# esp32_feather.net
KiCad netlist of a schematic drawn in EAGLE
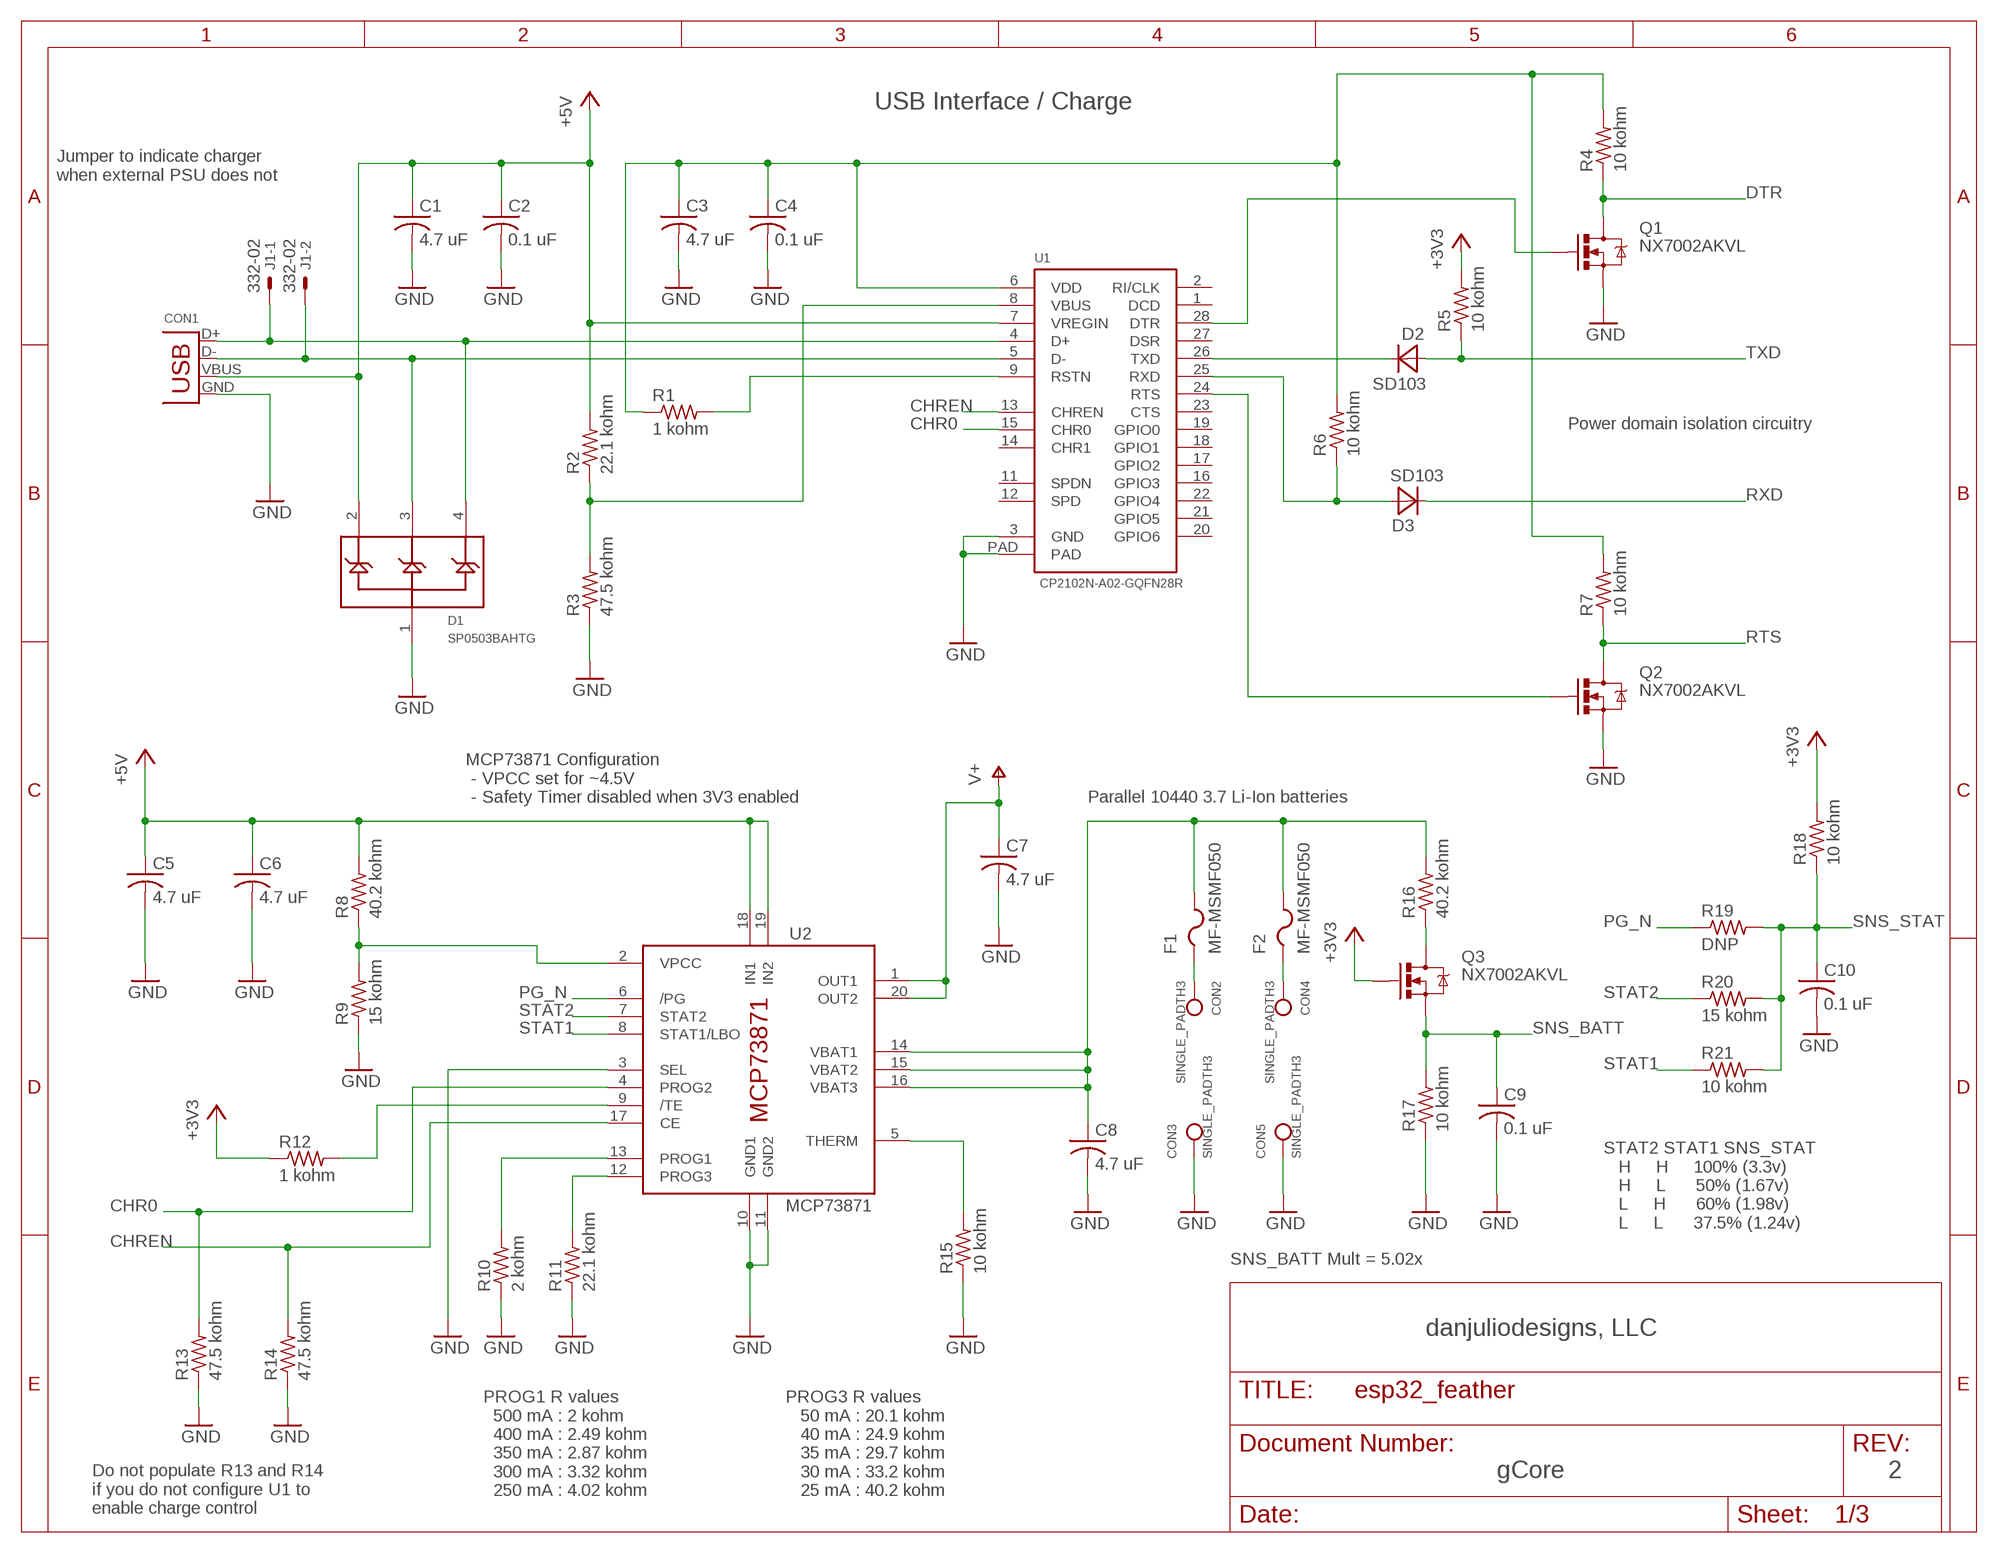
[diagram p0: schematic, sheet 1]
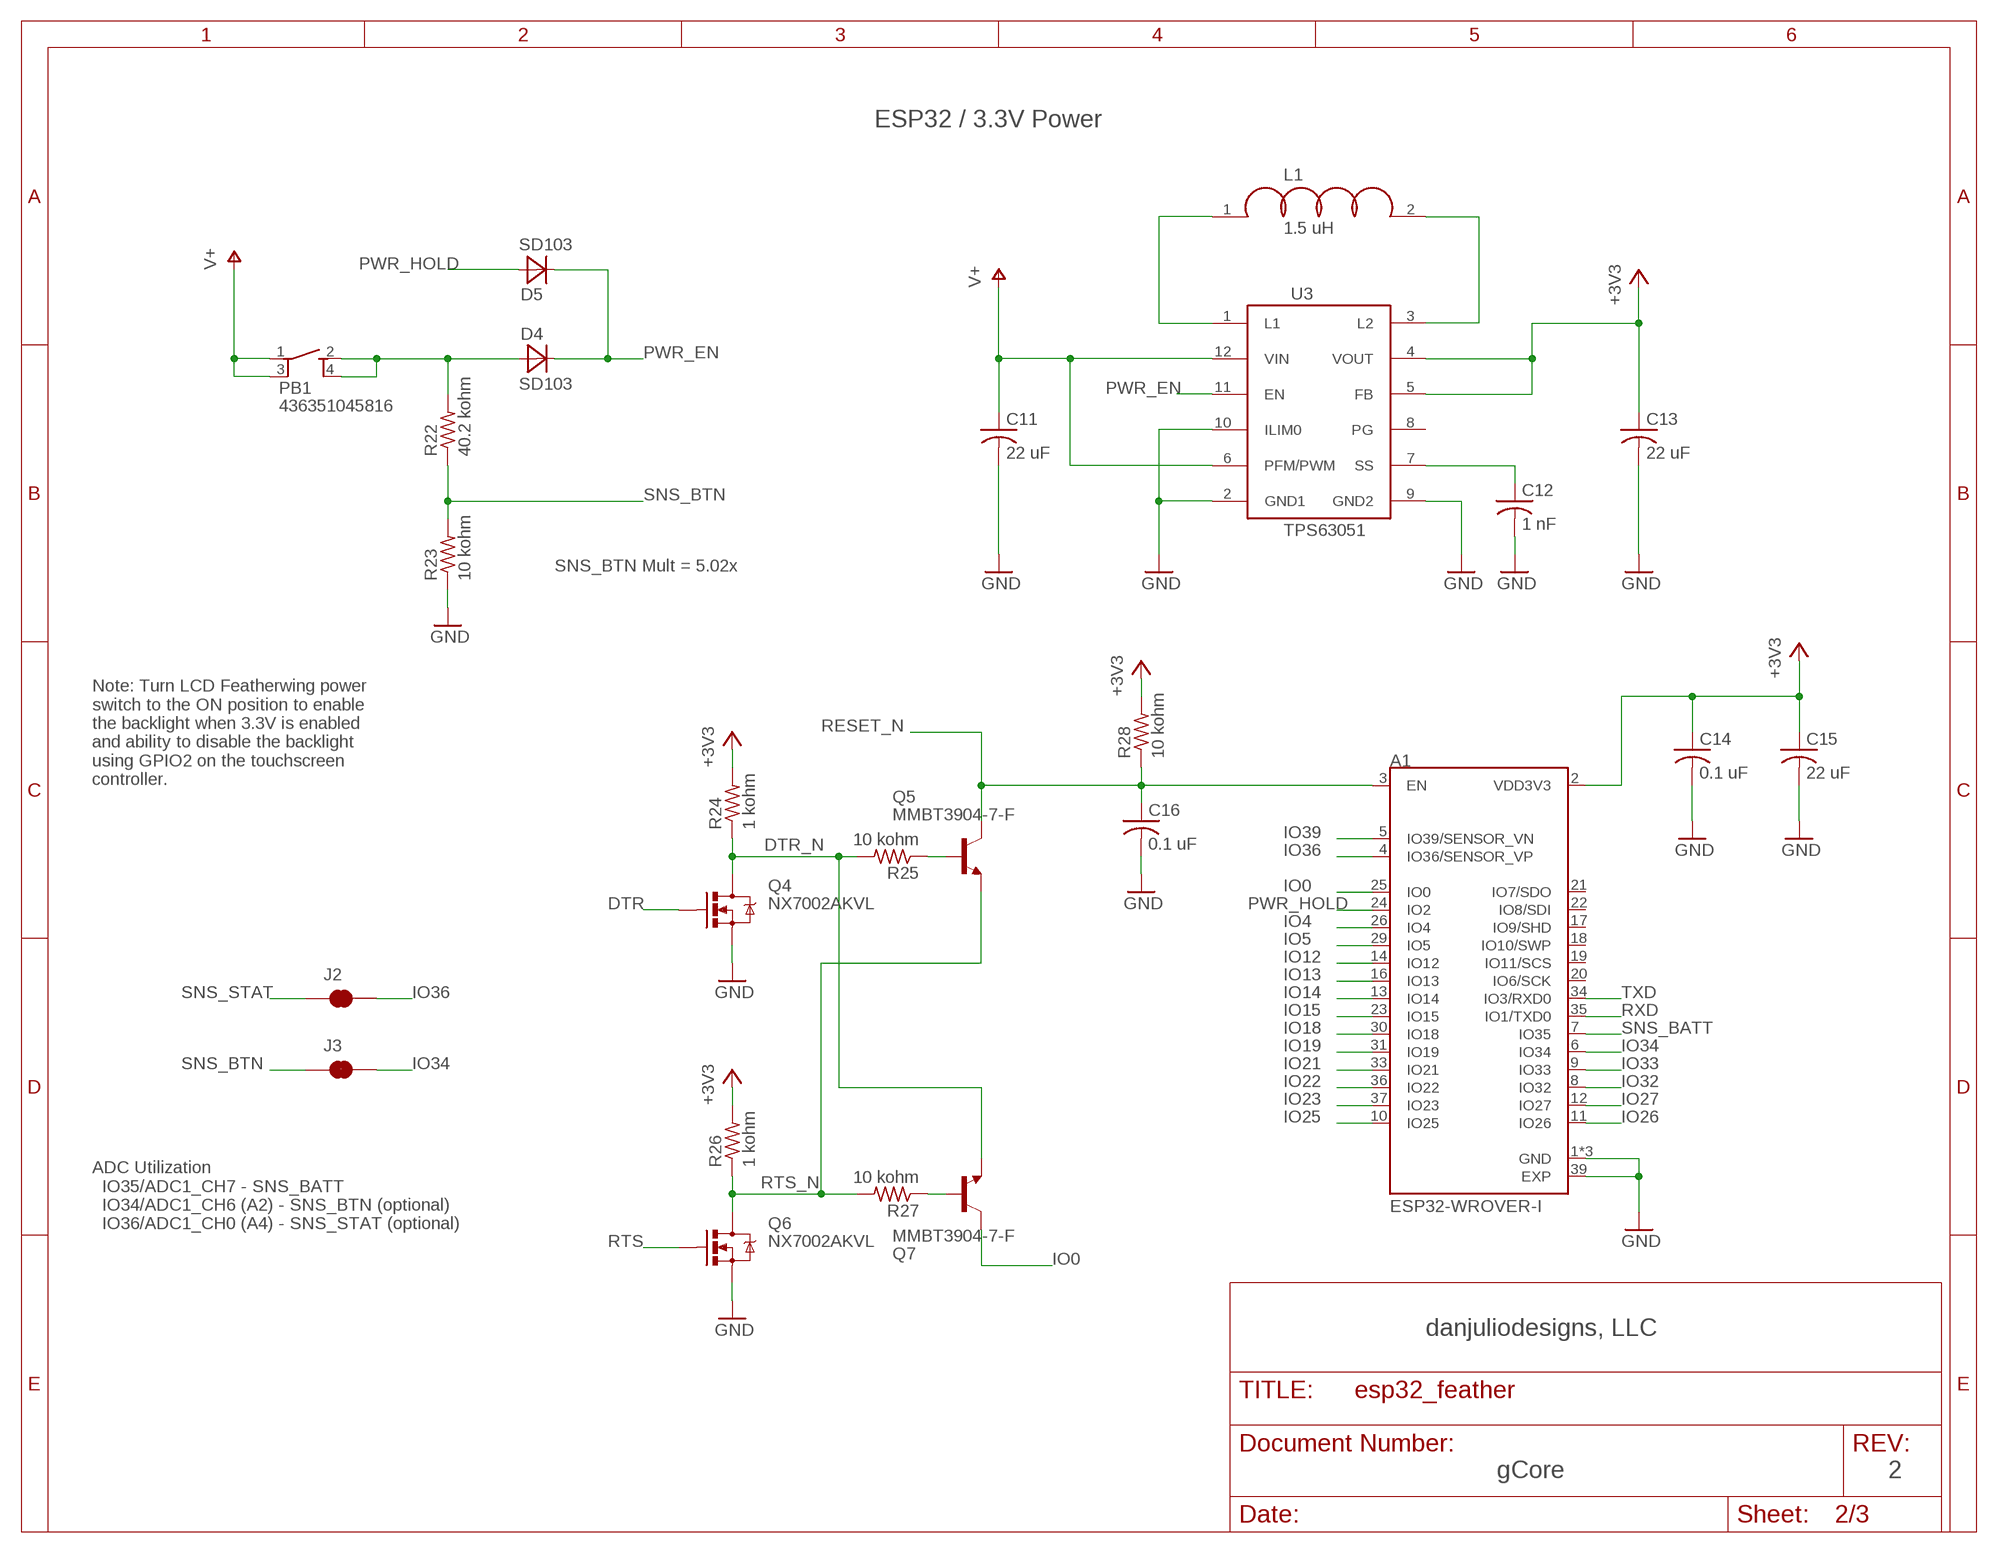
[diagram p1: schematic, sheet 2]
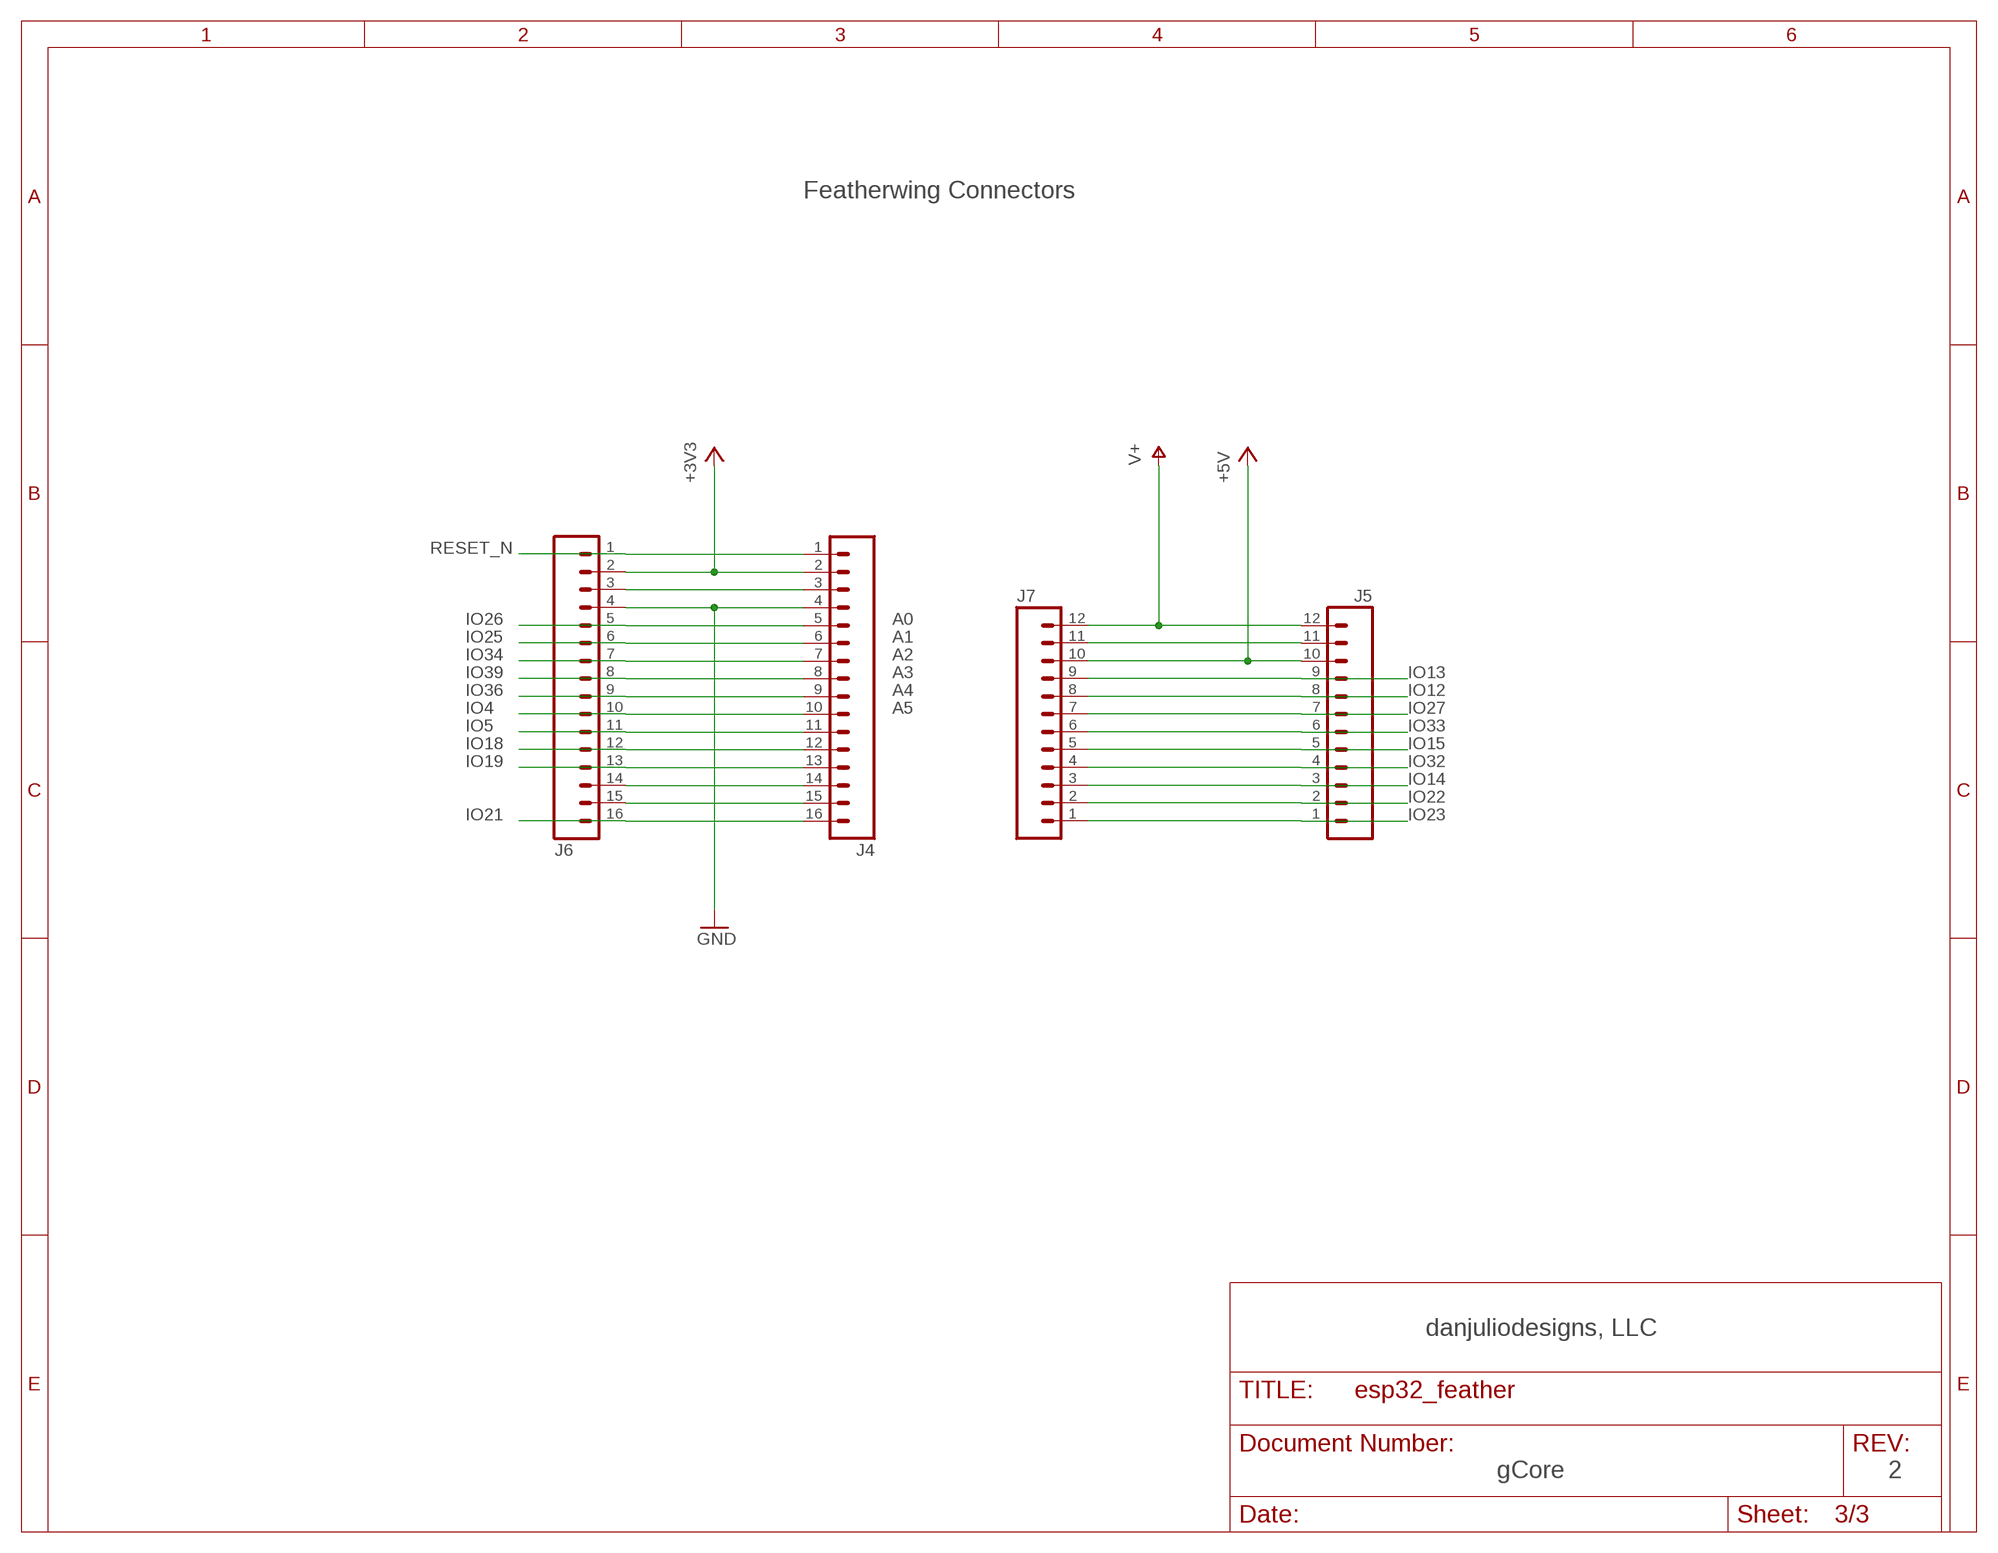
[diagram p2: schematic, sheet 3]

(export (version "E")
  (design (tool "Eeschema 10.0.6"))
  (components
    (comp (ref "C1")
      (value "4.7 uF")
      (footprint "eagle-import:C0603")
      (libsource (lib "eagle-import") (part "C-USSMT0603"))
    )
    (comp (ref "C2")
      (value "0.1 uF")
      (footprint "eagle-import:C0603")
      (libsource (lib "eagle-import") (part "C-USSMT0603"))
    )
    (comp (ref "C3")
      (value "4.7 uF")
      (footprint "eagle-import:C0603")
      (libsource (lib "eagle-import") (part "C-USSMT0603"))
    )
    (comp (ref "C4")
      (value "0.1 uF")
      (footprint "eagle-import:C0603")
      (libsource (lib "eagle-import") (part "C-USSMT0603"))
    )
    (comp (ref "C5")
      (value "4.7 uF")
      (footprint "eagle-import:C0603")
      (libsource (lib "eagle-import") (part "C-USSMT0603"))
    )
    (comp (ref "C6")
      (value "4.7 uF")
      (footprint "eagle-import:C0603")
      (libsource (lib "eagle-import") (part "C-USSMT0603"))
    )
    (comp (ref "C7")
      (value "4.7 uF")
      (footprint "eagle-import:C0603")
      (libsource (lib "eagle-import") (part "C-USSMT0603"))
    )
    (comp (ref "C8")
      (value "4.7 uF")
      (footprint "eagle-import:C0603")
      (libsource (lib "eagle-import") (part "C-USSMT0603"))
    )
    (comp (ref "C9")
      (value "0.1 uF")
      (footprint "eagle-import:C0603")
      (libsource (lib "eagle-import") (part "C-USSMT0603"))
    )
    (comp (ref "C10")
      (value "0.1 uF")
      (footprint "eagle-import:C0603")
      (libsource (lib "eagle-import") (part "C-USSMT0603"))
    )
    (comp (ref "CON1")
      (value "USBMICROB")
      (footprint "eagle-import:USB_MICROB_SMT")
      (libsource (lib "eagle-import") (part "USBMICROB"))
    )
    (comp (ref "CON2")
      (value "SINGLE_PADTH3")
      (footprint "eagle-import:SINGLE_PAD_POWER")
      (libsource (lib "eagle-import") (part "SINGLE_PADTH3"))
    )
    (comp (ref "CON3")
      (value "SINGLE_PADTH3")
      (footprint "eagle-import:SINGLE_PAD_POWER")
      (libsource (lib "eagle-import") (part "SINGLE_PADTH3"))
    )
    (comp (ref "CON4")
      (value "SINGLE_PADTH3")
      (footprint "eagle-import:SINGLE_PAD_POWER")
      (libsource (lib "eagle-import") (part "SINGLE_PADTH3"))
    )
    (comp (ref "CON5")
      (value "SINGLE_PADTH3")
      (footprint "eagle-import:SINGLE_PAD_POWER")
      (libsource (lib "eagle-import") (part "SINGLE_PADTH3"))
    )
    (comp (ref "D1")
      (value "SP0503BAHTG")
      (footprint "eagle-import:SOT143")
      (libsource (lib "eagle-import") (part "SP0503BAHTG"))
    )
    (comp (ref "D2")
      (value "SD103")
      (footprint "eagle-import:SOD123")
      (libsource (lib "eagle-import") (part "DIODESMT_SOD123"))
    )
    (comp (ref "D3")
      (value "SD103")
      (footprint "eagle-import:SOD123")
      (libsource (lib "eagle-import") (part "DIODESMT_SOD123"))
    )
    (comp (ref "F1")
      (value "MF-MSMF050")
      (footprint "eagle-import:1812")
      (libsource (lib "eagle-import") (part "PTCFUSE-1812"))
    )
    (comp (ref "F2")
      (value "MF-MSMF050")
      (footprint "eagle-import:1812")
      (libsource (lib "eagle-import") (part "PTCFUSE-1812"))
    )
    (comp (ref "J1")
      (value "332-02")
      (footprint "eagle-import:332-02")
      (libsource (lib "eagle-import") (part "332-02"))
    )
    (comp (ref "Q1")
      (value "NX7002AKVL")
      (footprint "eagle-import:SOT23-3")
      (libsource (lib "eagle-import") (part "MOSFET-NCHANNELSOT23"))
    )
    (comp (ref "Q2")
      (value "NX7002AKVL")
      (footprint "eagle-import:SOT23-3")
      (libsource (lib "eagle-import") (part "MOSFET-NCHANNELSOT23"))
    )
    (comp (ref "Q3")
      (value "NX7002AKVL")
      (footprint "eagle-import:SOT23-3")
      (libsource (lib "eagle-import") (part "MOSFET-NCHANNELSOT23"))
    )
    (comp (ref "R1")
      (value "1 kohm")
      (footprint "eagle-import:R0603")
      (libsource (lib "eagle-import") (part "R-USSMT0603"))
    )
    (comp (ref "R2")
      (value "22.1 kohm")
      (footprint "eagle-import:R0603")
      (libsource (lib "eagle-import") (part "R-USSMT0603"))
    )
    (comp (ref "R3")
      (value "47.5 kohm")
      (footprint "eagle-import:R0603")
      (libsource (lib "eagle-import") (part "R-USSMT0603"))
    )
    (comp (ref "R4")
      (value "10 kohm")
      (footprint "eagle-import:R0603")
      (libsource (lib "eagle-import") (part "R-USSMT0603"))
    )
    (comp (ref "R5")
      (value "10 kohm")
      (footprint "eagle-import:R0603")
      (libsource (lib "eagle-import") (part "R-USSMT0603"))
    )
    (comp (ref "R6")
      (value "10 kohm")
      (footprint "eagle-import:R0603")
      (libsource (lib "eagle-import") (part "R-USSMT0603"))
    )
    (comp (ref "R7")
      (value "10 kohm")
      (footprint "eagle-import:R0603")
      (libsource (lib "eagle-import") (part "R-USSMT0603"))
    )
    (comp (ref "R8")
      (value "40.2 kohm")
      (footprint "eagle-import:R0603")
      (libsource (lib "eagle-import") (part "R-USSMT0603"))
    )
    (comp (ref "R9")
      (value "15 kohm")
      (footprint "eagle-import:R0603")
      (libsource (lib "eagle-import") (part "R-USSMT0603"))
    )
    (comp (ref "R10")
      (value "2 kohm")
      (footprint "eagle-import:R0603")
      (libsource (lib "eagle-import") (part "R-USSMT0603"))
    )
    (comp (ref "R11")
      (value "22.1 kohm")
      (footprint "eagle-import:R0603")
      (libsource (lib "eagle-import") (part "R-USSMT0603"))
    )
    (comp (ref "R12")
      (value "1 kohm")
      (footprint "eagle-import:R0603")
      (libsource (lib "eagle-import") (part "R-USSMT0603"))
    )
    (comp (ref "R13")
      (value "47.5 kohm")
      (footprint "eagle-import:R0603")
      (libsource (lib "eagle-import") (part "R-USSMT0603"))
    )
    (comp (ref "R14")
      (value "47.5 kohm")
      (footprint "eagle-import:R0603")
      (libsource (lib "eagle-import") (part "R-USSMT0603"))
    )
    (comp (ref "R15")
      (value "10 kohm")
      (footprint "eagle-import:R0603")
      (libsource (lib "eagle-import") (part "R-USSMT0603"))
    )
    (comp (ref "R16")
      (value "40.2 kohm")
      (footprint "eagle-import:R0603")
      (libsource (lib "eagle-import") (part "R-USSMT0603"))
    )
    (comp (ref "R17")
      (value "10 kohm")
      (footprint "eagle-import:R0603")
      (libsource (lib "eagle-import") (part "R-USSMT0603"))
    )
    (comp (ref "R18")
      (value "10 kohm")
      (footprint "eagle-import:R0603")
      (libsource (lib "eagle-import") (part "R-USSMT0603"))
    )
    (comp (ref "R19")
      (value "DNP")
      (footprint "eagle-import:R0603")
      (libsource (lib "eagle-import") (part "R-USSMT0603"))
    )
    (comp (ref "R20")
      (value "15 kohm")
      (footprint "eagle-import:R0603")
      (libsource (lib "eagle-import") (part "R-USSMT0603"))
    )
    (comp (ref "R21")
      (value "10 kohm")
      (footprint "eagle-import:R0603")
      (libsource (lib "eagle-import") (part "R-USSMT0603"))
    )
    (comp (ref "U1")
      (value "CP2102N-A02-GQFN28R")
      (footprint "eagle-import:QFN28")
      (libsource (lib "eagle-import") (part "CP2102N_QFN28"))
    )
    (comp (ref "U2")
      (value "MCP73871")
      (footprint "eagle-import:QFN20")
      (libsource (lib "eagle-import") (part "MCP73871"))
    )
    (comp (ref "A1")
      (value "ESP32-WROVER-I")
      (footprint "eagle-import:XCVR_ESP32-WROVER-I")
      (fields (field (name "MF") "Espressif Systems"))
      (libsource (lib "eagle-import") (part "ESP32-WROVER-I"))
    )
    (comp (ref "C11")
      (value "22 uF")
      (footprint "eagle-import:C0603")
      (libsource (lib "eagle-import") (part "C-USSMT0603"))
    )
    (comp (ref "C12")
      (value "1 nF")
      (footprint "eagle-import:C0603")
      (libsource (lib "eagle-import") (part "C-USSMT0603"))
    )
    (comp (ref "C13")
      (value "22 uF")
      (footprint "eagle-import:C0603")
      (libsource (lib "eagle-import") (part "C-USSMT0603"))
    )
    (comp (ref "C14")
      (value "0.1 uF")
      (footprint "eagle-import:C0603")
      (libsource (lib "eagle-import") (part "C-USSMT0603"))
    )
    (comp (ref "C15")
      (value "22 uF")
      (footprint "eagle-import:C0603")
      (libsource (lib "eagle-import") (part "C-USSMT0603"))
    )
    (comp (ref "C16")
      (value "0.1 uF")
      (footprint "eagle-import:C0603")
      (libsource (lib "eagle-import") (part "C-USSMT0603"))
    )
    (comp (ref "D4")
      (value "SD103")
      (footprint "eagle-import:SOD123")
      (libsource (lib "eagle-import") (part "DIODESMT_SOD123"))
    )
    (comp (ref "D5")
      (value "SD103")
      (footprint "eagle-import:SOD123")
      (libsource (lib "eagle-import") (part "DIODESMT_SOD123"))
    )
    (comp (ref "J2")
      (value "SJ_WIRED")
      (footprint "eagle-import:SJ_2B_ADA")
      (libsource (lib "eagle-import") (part "SJ_WIRED"))
    )
    (comp (ref "J3")
      (value "SJ_WIRED")
      (footprint "eagle-import:SJ_2B_ADA")
      (libsource (lib "eagle-import") (part "SJ_WIRED"))
    )
    (comp (ref "L1")
      (value "1.5 uH")
      (footprint "eagle-import:L1008")
      (libsource (lib "eagle-import") (part "INDUCTORSMT1008"))
    )
    (comp (ref "PB1")
      (value "436351045816")
      (footprint "eagle-import:WURTH_WS_TASU_TACT")
      (libsource (lib "eagle-import") (part "PB_TACT_4WS"))
    )
    (comp (ref "Q4")
      (value "NX7002AKVL")
      (footprint "eagle-import:SOT23-3")
      (libsource (lib "eagle-import") (part "MOSFET-NCHANNELSOT23"))
    )
    (comp (ref "Q5")
      (value "MMBT3904-7-F")
      (footprint "eagle-import:SOT23-BEC")
      (libsource (lib "eagle-import") (part "-NPN-SOT23-BECBC808"))
    )
    (comp (ref "Q6")
      (value "NX7002AKVL")
      (footprint "eagle-import:SOT23-3")
      (libsource (lib "eagle-import") (part "MOSFET-NCHANNELSOT23"))
    )
    (comp (ref "Q7")
      (value "MMBT3904-7-F")
      (footprint "eagle-import:SOT23-BEC")
      (libsource (lib "eagle-import") (part "-NPN-SOT23-BECBC808"))
    )
    (comp (ref "R22")
      (value "40.2 kohm")
      (footprint "eagle-import:R0603")
      (libsource (lib "eagle-import") (part "R-USSMT0603"))
    )
    (comp (ref "R23")
      (value "10 kohm")
      (footprint "eagle-import:R0603")
      (libsource (lib "eagle-import") (part "R-USSMT0603"))
    )
    (comp (ref "R24")
      (value "1 kohm")
      (footprint "eagle-import:R0603")
      (libsource (lib "eagle-import") (part "R-USSMT0603"))
    )
    (comp (ref "R25")
      (value "10 kohm")
      (footprint "eagle-import:R0603")
      (libsource (lib "eagle-import") (part "R-USSMT0603"))
    )
    (comp (ref "R26")
      (value "1 kohm")
      (footprint "eagle-import:R0603")
      (libsource (lib "eagle-import") (part "R-USSMT0603"))
    )
    (comp (ref "R27")
      (value "10 kohm")
      (footprint "eagle-import:R0603")
      (libsource (lib "eagle-import") (part "R-USSMT0603"))
    )
    (comp (ref "R28")
      (value "10 kohm")
      (footprint "eagle-import:R0603")
      (libsource (lib "eagle-import") (part "R-USSMT0603"))
    )
    (comp (ref "U3")
      (value "TPS63051")
      (footprint "eagle-import:HOTROD_QFN12")
      (libsource (lib "eagle-import") (part "TPS63051_QFN"))
    )
    (comp (ref "J4")
      (value "M16PTH")
      (footprint "eagle-import:1X16")
      (libsource (lib "eagle-import") (part "M16PTH"))
    )
    (comp (ref "J5")
      (value "M12PTH")
      (footprint "eagle-import:1X12")
      (libsource (lib "eagle-import") (part "M12PTH"))
    )
    (comp (ref "J6")
      (value "M16PTH")
      (footprint "eagle-import:1X16")
      (libsource (lib "eagle-import") (part "M16PTH"))
    )
    (comp (ref "J7")
      (value "M12PTH")
      (footprint "eagle-import:1X12")
      (libsource (lib "eagle-import") (part "M12PTH"))
    )
  )
  (nets
    (net (code "1") (name "+3V3") (class "Default")
      (node (ref "A1") (pin "2") (pinfunction "VDD3V3_2") (pintype "power_in"))
      (node (ref "C13") (pin "1") (pinfunction "1_1") (pintype "passive"))
      (node (ref "C14") (pin "1") (pinfunction "1_1") (pintype "passive"))
      (node (ref "C15") (pin "1") (pinfunction "1_1") (pintype "passive"))
      (node (ref "J4") (pin "2") (pinfunction "2_2") (pintype "passive"))
      (node (ref "J6") (pin "2") (pinfunction "2_2") (pintype "passive"))
      (node (ref "Q3") (pin "1") (pinfunction "G_1") (pintype "passive"))
      (node (ref "R12") (pin "1") (pinfunction "1_1") (pintype "passive"))
      (node (ref "R18") (pin "2") (pinfunction "2_2") (pintype "passive"))
      (node (ref "R24") (pin "2") (pinfunction "2_2") (pintype "passive"))
      (node (ref "R26") (pin "2") (pinfunction "2_2") (pintype "passive"))
      (node (ref "R28") (pin "2") (pinfunction "2_2") (pintype "passive"))
      (node (ref "R5") (pin "2") (pinfunction "2_2") (pintype "passive"))
      (node (ref "U3") (pin "4") (pinfunction "VOUT_4") (pintype "bidirectional"))
      (node (ref "U3") (pin "5") (pinfunction "FB_5") (pintype "passive"))
    )
    (net (code "2") (name "+5V") (class "Default")
      (node (ref "C1") (pin "1") (pinfunction "1_1") (pintype "passive"))
      (node (ref "C2") (pin "1") (pinfunction "1_1") (pintype "passive"))
      (node (ref "C5") (pin "1") (pinfunction "1_1") (pintype "passive"))
      (node (ref "C6") (pin "1") (pinfunction "1_1") (pintype "passive"))
      (node (ref "CON1") (pin "VBUS") (pinfunction "VBUS_VBUS") (pintype "bidirectional"))
      (node (ref "D1") (pin "2") (pinfunction "C1_2") (pintype "passive"))
      (node (ref "J5") (pin "10") (pinfunction "10_10") (pintype "passive"))
      (node (ref "J7") (pin "10") (pinfunction "10_10") (pintype "passive"))
      (node (ref "R2") (pin "2") (pinfunction "2_2") (pintype "passive"))
      (node (ref "R8") (pin "2") (pinfunction "2_2") (pintype "passive"))
      (node (ref "U1") (pin "7") (pinfunction "VREGIN_7") (pintype "power_in"))
      (node (ref "U2") (pin "18") (pinfunction "IN1_18") (pintype "input"))
      (node (ref "U2") (pin "19") (pinfunction "IN2_19") (pintype "input"))
    )
    (net (code "3") (name "CHR0") (class "Default")
      (node (ref "R13") (pin "2") (pinfunction "2_2") (pintype "passive"))
      (node (ref "U1") (pin "15") (pinfunction "CHR0_15") (pintype "output"))
      (node (ref "U2") (pin "4") (pinfunction "PROG2_4") (pintype "input"))
    )
    (net (code "4") (name "CHREN") (class "Default")
      (node (ref "R14") (pin "2") (pinfunction "2_2") (pintype "passive"))
      (node (ref "U1") (pin "13") (pinfunction "CHREN_13") (pintype "output"))
      (node (ref "U2") (pin "17") (pinfunction "CE_17") (pintype "input"))
    )
    (net (code "5") (name "DTR") (class "Default")
      (node (ref "Q1") (pin "3") (pinfunction "D_3") (pintype "passive"))
      (node (ref "Q4") (pin "1") (pinfunction "G_1") (pintype "passive"))
      (node (ref "R4") (pin "1") (pinfunction "1_1") (pintype "passive"))
    )
    (net (code "6") (name "DTR_N") (class "Default")
      (node (ref "Q4") (pin "3") (pinfunction "D_3") (pintype "passive"))
      (node (ref "Q7") (pin "E") (pinfunction "E_E") (pintype "passive"))
      (node (ref "R24") (pin "1") (pinfunction "1_1") (pintype "passive"))
      (node (ref "R25") (pin "2") (pinfunction "2_2") (pintype "passive"))
    )
    (net (code "7") (name "GND") (class "Default")
      (node (ref "A1") (pin "1") (pinfunction "GND_1") (pintype "power_in"))
      (node (ref "A1") (pin "15") (pinfunction "GND_15") (pintype "power_in"))
      (node (ref "A1") (pin "38") (pinfunction "GND_38") (pintype "power_in"))
      (node (ref "A1") (pin "39") (pinfunction "EXP_39") (pintype "power_in"))
      (node (ref "C1") (pin "2") (pinfunction "2_2") (pintype "passive"))
      (node (ref "C10") (pin "2") (pinfunction "2_2") (pintype "passive"))
      (node (ref "C11") (pin "2") (pinfunction "2_2") (pintype "passive"))
      (node (ref "C12") (pin "2") (pinfunction "2_2") (pintype "passive"))
      (node (ref "C13") (pin "2") (pinfunction "2_2") (pintype "passive"))
      (node (ref "C14") (pin "2") (pinfunction "2_2") (pintype "passive"))
      (node (ref "C15") (pin "2") (pinfunction "2_2") (pintype "passive"))
      (node (ref "C16") (pin "2") (pinfunction "2_2") (pintype "passive"))
      (node (ref "C2") (pin "2") (pinfunction "2_2") (pintype "passive"))
      (node (ref "C3") (pin "2") (pinfunction "2_2") (pintype "passive"))
      (node (ref "C4") (pin "2") (pinfunction "2_2") (pintype "passive"))
      (node (ref "C5") (pin "2") (pinfunction "2_2") (pintype "passive"))
      (node (ref "C6") (pin "2") (pinfunction "2_2") (pintype "passive"))
      (node (ref "C7") (pin "2") (pinfunction "2_2") (pintype "passive"))
      (node (ref "C8") (pin "2") (pinfunction "2_2") (pintype "passive"))
      (node (ref "C9") (pin "2") (pinfunction "2_2") (pintype "passive"))
      (node (ref "CON1") (pin "GND") (pinfunction "GND_GND") (pintype "bidirectional"))
      (node (ref "CON3") (pin "P$1") (pinfunction "P$1_P$1") (pintype "passive"))
      (node (ref "CON5") (pin "P$1") (pinfunction "P$1_P$1") (pintype "passive"))
      (node (ref "D1") (pin "1") (pinfunction "GND_1") (pintype "power_in"))
      (node (ref "J4") (pin "4") (pinfunction "4_4") (pintype "passive"))
      (node (ref "J6") (pin "4") (pinfunction "4_4") (pintype "passive"))
      (node (ref "Q1") (pin "2") (pinfunction "S_2") (pintype "passive"))
      (node (ref "Q2") (pin "2") (pinfunction "S_2") (pintype "passive"))
      (node (ref "Q4") (pin "2") (pinfunction "S_2") (pintype "passive"))
      (node (ref "Q6") (pin "2") (pinfunction "S_2") (pintype "passive"))
      (node (ref "R10") (pin "1") (pinfunction "1_1") (pintype "passive"))
      (node (ref "R11") (pin "1") (pinfunction "1_1") (pintype "passive"))
      (node (ref "R13") (pin "1") (pinfunction "1_1") (pintype "passive"))
      (node (ref "R14") (pin "1") (pinfunction "1_1") (pintype "passive"))
      (node (ref "R15") (pin "1") (pinfunction "1_1") (pintype "passive"))
      (node (ref "R17") (pin "1") (pinfunction "1_1") (pintype "passive"))
      (node (ref "R23") (pin "1") (pinfunction "1_1") (pintype "passive"))
      (node (ref "R3") (pin "1") (pinfunction "1_1") (pintype "passive"))
      (node (ref "R9") (pin "1") (pinfunction "1_1") (pintype "passive"))
      (node (ref "U1") (pin "3") (pinfunction "GND_3") (pintype "power_in"))
      (node (ref "U1") (pin "PAD") (pinfunction "PAD_PAD") (pintype "power_in"))
      (node (ref "U2") (pin "10") (pinfunction "GND1_10") (pintype "power_in"))
      (node (ref "U2") (pin "11") (pinfunction "GND2_11") (pintype "power_in"))
      (node (ref "U2") (pin "3") (pinfunction "SEL_3") (pintype "input"))
      (node (ref "U3") (pin "10") (pinfunction "ILIM0_10") (pintype "bidirectional"))
      (node (ref "U3") (pin "2") (pinfunction "GND1_2") (pintype "power_in"))
      (node (ref "U3") (pin "9") (pinfunction "GND2_9") (pintype "power_in"))
    )
    (net (code "8") (name "IO0") (class "Default")
      (node (ref "A1") (pin "25") (pinfunction "IO0_25") (pintype "bidirectional"))
      (node (ref "Q7") (pin "C") (pinfunction "C_C") (pintype "passive"))
    )
    (net (code "9") (name "IO4") (class "Default")
      (node (ref "A1") (pin "26") (pinfunction "IO4_26") (pintype "bidirectional"))
      (node (ref "J4") (pin "10") (pinfunction "10_10") (pintype "passive"))
      (node (ref "J6") (pin "10") (pinfunction "10_10") (pintype "passive"))
    )
    (net (code "10") (name "IO5") (class "Default")
      (node (ref "A1") (pin "29") (pinfunction "IO5_29") (pintype "bidirectional"))
      (node (ref "J4") (pin "11") (pinfunction "11_11") (pintype "passive"))
      (node (ref "J6") (pin "11") (pinfunction "11_11") (pintype "passive"))
    )
    (net (code "11") (name "IO12") (class "Default")
      (node (ref "A1") (pin "14") (pinfunction "IO12_14") (pintype "bidirectional"))
      (node (ref "J5") (pin "8") (pinfunction "8_8") (pintype "passive"))
      (node (ref "J7") (pin "8") (pinfunction "8_8") (pintype "passive"))
    )
    (net (code "12") (name "IO13") (class "Default")
      (node (ref "A1") (pin "16") (pinfunction "IO13_16") (pintype "bidirectional"))
      (node (ref "J5") (pin "9") (pinfunction "9_9") (pintype "passive"))
      (node (ref "J7") (pin "9") (pinfunction "9_9") (pintype "passive"))
    )
    (net (code "13") (name "IO14") (class "Default")
      (node (ref "A1") (pin "13") (pinfunction "IO14_13") (pintype "bidirectional"))
      (node (ref "J5") (pin "3") (pinfunction "3_3") (pintype "passive"))
      (node (ref "J7") (pin "3") (pinfunction "3_3") (pintype "passive"))
    )
    (net (code "14") (name "IO15") (class "Default")
      (node (ref "A1") (pin "23") (pinfunction "IO15_23") (pintype "bidirectional"))
      (node (ref "J5") (pin "5") (pinfunction "5_5") (pintype "passive"))
      (node (ref "J7") (pin "5") (pinfunction "5_5") (pintype "passive"))
    )
    (net (code "15") (name "IO18") (class "Default")
      (node (ref "A1") (pin "30") (pinfunction "IO18_30") (pintype "bidirectional"))
      (node (ref "J4") (pin "12") (pinfunction "12_12") (pintype "passive"))
      (node (ref "J6") (pin "12") (pinfunction "12_12") (pintype "passive"))
    )
    (net (code "16") (name "IO19") (class "Default")
      (node (ref "A1") (pin "31") (pinfunction "IO19_31") (pintype "bidirectional"))
      (node (ref "J4") (pin "13") (pinfunction "13_13") (pintype "passive"))
      (node (ref "J6") (pin "13") (pinfunction "13_13") (pintype "passive"))
    )
    (net (code "17") (name "IO21") (class "Default")
      (node (ref "A1") (pin "33") (pinfunction "IO21_33") (pintype "bidirectional"))
      (node (ref "J4") (pin "16") (pinfunction "16_16") (pintype "passive"))
      (node (ref "J6") (pin "16") (pinfunction "16_16") (pintype "passive"))
    )
    (net (code "18") (name "IO22") (class "Default")
      (node (ref "A1") (pin "36") (pinfunction "IO22_36") (pintype "bidirectional"))
      (node (ref "J5") (pin "2") (pinfunction "2_2") (pintype "passive"))
      (node (ref "J7") (pin "2") (pinfunction "2_2") (pintype "passive"))
    )
    (net (code "19") (name "IO23") (class "Default")
      (node (ref "A1") (pin "37") (pinfunction "IO23_37") (pintype "bidirectional"))
      (node (ref "J5") (pin "1") (pinfunction "1_1") (pintype "passive"))
      (node (ref "J7") (pin "1") (pinfunction "1_1") (pintype "passive"))
    )
    (net (code "20") (name "IO25") (class "Default")
      (node (ref "A1") (pin "10") (pinfunction "IO25_10") (pintype "bidirectional"))
      (node (ref "J4") (pin "6") (pinfunction "6_6") (pintype "passive"))
      (node (ref "J6") (pin "6") (pinfunction "6_6") (pintype "passive"))
    )
    (net (code "21") (name "IO26") (class "Default")
      (node (ref "A1") (pin "11") (pinfunction "IO26_11") (pintype "bidirectional"))
      (node (ref "J4") (pin "5") (pinfunction "5_5") (pintype "passive"))
      (node (ref "J6") (pin "5") (pinfunction "5_5") (pintype "passive"))
    )
    (net (code "22") (name "IO27") (class "Default")
      (node (ref "A1") (pin "12") (pinfunction "IO27_12") (pintype "bidirectional"))
      (node (ref "J5") (pin "7") (pinfunction "7_7") (pintype "passive"))
      (node (ref "J7") (pin "7") (pinfunction "7_7") (pintype "passive"))
    )
    (net (code "23") (name "IO32") (class "Default")
      (node (ref "A1") (pin "8") (pinfunction "IO32_8") (pintype "bidirectional"))
      (node (ref "J5") (pin "4") (pinfunction "4_4") (pintype "passive"))
      (node (ref "J7") (pin "4") (pinfunction "4_4") (pintype "passive"))
    )
    (net (code "24") (name "IO33") (class "Default")
      (node (ref "A1") (pin "9") (pinfunction "IO33_9") (pintype "bidirectional"))
      (node (ref "J5") (pin "6") (pinfunction "6_6") (pintype "passive"))
      (node (ref "J7") (pin "6") (pinfunction "6_6") (pintype "passive"))
    )
    (net (code "25") (name "IO34") (class "Default")
      (node (ref "A1") (pin "6") (pinfunction "IO34_6") (pintype "input"))
      (node (ref "J3") (pin "2") (pinfunction "2_2") (pintype "passive"))
      (node (ref "J4") (pin "7") (pinfunction "7_7") (pintype "passive"))
      (node (ref "J6") (pin "7") (pinfunction "7_7") (pintype "passive"))
    )
    (net (code "26") (name "IO36") (class "Default")
      (node (ref "A1") (pin "4") (pinfunction "IO36/SENSOR_VP_4") (pintype "input"))
      (node (ref "J2") (pin "2") (pinfunction "2_2") (pintype "passive"))
      (node (ref "J4") (pin "9") (pinfunction "9_9") (pintype "passive"))
      (node (ref "J6") (pin "9") (pinfunction "9_9") (pintype "passive"))
    )
    (net (code "27") (name "IO39") (class "Default")
      (node (ref "A1") (pin "5") (pinfunction "IO39/SENSOR_VN_5") (pintype "input"))
      (node (ref "J4") (pin "8") (pinfunction "8_8") (pintype "passive"))
      (node (ref "J6") (pin "8") (pinfunction "8_8") (pintype "passive"))
    )
    (net (code "28") (name "Net-(CON2-PadP$1)") (class "Default")
      (node (ref "CON2") (pin "P$1") (pinfunction "P$1_P$1") (pintype "passive"))
      (node (ref "F1") (pin "1") (pinfunction "1_1") (pintype "passive"))
    )
    (net (code "29") (name "Net-(CON4-PadP$1)") (class "Default")
      (node (ref "CON4") (pin "P$1") (pinfunction "P$1_P$1") (pintype "passive"))
      (node (ref "F2") (pin "1") (pinfunction "1_1") (pintype "passive"))
    )
    (net (code "30") (name "Net-(D1-C2)") (class "Default")
      (node (ref "CON1") (pin "D-") (pinfunction "D-_D-") (pintype "bidirectional"))
      (node (ref "D1") (pin "3") (pinfunction "C2_3") (pintype "passive"))
      (node (ref "J1") (pin "2") (pinfunction "S_2") (pintype "passive"))
      (node (ref "U1") (pin "5") (pinfunction "D-_5") (pintype "bidirectional"))
    )
    (net (code "31") (name "Net-(D1-C3)") (class "Default")
      (node (ref "CON1") (pin "D+") (pinfunction "D+_D+") (pintype "bidirectional"))
      (node (ref "D1") (pin "4") (pinfunction "C3_4") (pintype "passive"))
      (node (ref "J1") (pin "1") (pinfunction "S_1") (pintype "passive"))
      (node (ref "U1") (pin "4") (pinfunction "D+_4") (pintype "bidirectional"))
    )
    (net (code "32") (name "Net-(J4-Pad3)") (class "Default")
      (node (ref "J4") (pin "3") (pinfunction "3_3") (pintype "passive"))
      (node (ref "J6") (pin "3") (pinfunction "3_3") (pintype "passive"))
    )
    (net (code "33") (name "Net-(J4-Pad14)") (class "Default")
      (node (ref "J4") (pin "14") (pinfunction "14_14") (pintype "passive"))
      (node (ref "J6") (pin "14") (pinfunction "14_14") (pintype "passive"))
    )
    (net (code "34") (name "Net-(J4-Pad15)") (class "Default")
      (node (ref "J4") (pin "15") (pinfunction "15_15") (pintype "passive"))
      (node (ref "J6") (pin "15") (pinfunction "15_15") (pintype "passive"))
    )
    (net (code "35") (name "Net-(J5-Pad11)") (class "Default")
      (node (ref "J5") (pin "11") (pinfunction "11_11") (pintype "passive"))
      (node (ref "J7") (pin "11") (pinfunction "11_11") (pintype "passive"))
    )
    (net (code "36") (name "Net-(L1-P$1)") (class "Default")
      (node (ref "L1") (pin "1") (pinfunction "P$1_1") (pintype "passive"))
      (node (ref "U3") (pin "1") (pinfunction "L1_1") (pintype "passive"))
    )
    (net (code "37") (name "Net-(L1-P$2)") (class "Default")
      (node (ref "L1") (pin "2") (pinfunction "P$2_2") (pintype "passive"))
      (node (ref "U3") (pin "3") (pinfunction "L2_3") (pintype "passive"))
    )
    (net (code "38") (name "Net-(PB1-3)") (class "Default")
      (node (ref "D4") (pin "A") (pinfunction "A_A") (pintype "passive"))
      (node (ref "PB1") (pin "2") (pinfunction "3_2") (pintype "passive"))
      (node (ref "PB1") (pin "4") (pinfunction "4_4") (pintype "passive"))
      (node (ref "R22") (pin "2") (pinfunction "2_2") (pintype "passive"))
    )
    (net (code "39") (name "Net-(Q1-G)") (class "Default")
      (node (ref "Q1") (pin "1") (pinfunction "G_1") (pintype "passive"))
      (node (ref "U1") (pin "28") (pinfunction "DTR_28") (pintype "output"))
    )
    (net (code "40") (name "Net-(Q2-G)") (class "Default")
      (node (ref "Q2") (pin "1") (pinfunction "G_1") (pintype "passive"))
      (node (ref "U1") (pin "24") (pinfunction "RTS_24") (pintype "output"))
    )
    (net (code "41") (name "Net-(Q3-D)") (class "Default")
      (node (ref "Q3") (pin "3") (pinfunction "D_3") (pintype "passive"))
      (node (ref "R16") (pin "1") (pinfunction "1_1") (pintype "passive"))
    )
    (net (code "42") (name "Net-(Q5-PadB)") (class "Default")
      (node (ref "Q5") (pin "B") (pinfunction "B_B") (pintype "passive"))
      (node (ref "R25") (pin "1") (pinfunction "1_1") (pintype "passive"))
    )
    (net (code "43") (name "Net-(Q7-PadB)") (class "Default")
      (node (ref "Q7") (pin "B") (pinfunction "B_B") (pintype "passive"))
      (node (ref "R27") (pin "1") (pinfunction "1_1") (pintype "passive"))
    )
    (net (code "44") (name "Net-(U1-RSTN)") (class "Default")
      (node (ref "R1") (pin "2") (pinfunction "2_2") (pintype "passive"))
      (node (ref "U1") (pin "9") (pinfunction "RSTN_9") (pintype "input"))
    )
    (net (code "45") (name "Net-(U1-RXD)") (class "Default")
      (node (ref "D3") (pin "A") (pinfunction "A_A") (pintype "passive"))
      (node (ref "R6") (pin "1") (pinfunction "1_1") (pintype "passive"))
      (node (ref "U1") (pin "25") (pinfunction "RXD_25") (pintype "input"))
    )
    (net (code "46") (name "Net-(U1-TXD)") (class "Default")
      (node (ref "D2") (pin "C") (pinfunction "C_C") (pintype "passive"))
      (node (ref "U1") (pin "26") (pinfunction "TXD_26") (pintype "output"))
    )
    (net (code "47") (name "Net-(U1-VBUS)") (class "Default")
      (node (ref "R2") (pin "1") (pinfunction "1_1") (pintype "passive"))
      (node (ref "R3") (pin "2") (pinfunction "2_2") (pintype "passive"))
      (node (ref "U1") (pin "8") (pinfunction "VBUS_8") (pintype "input"))
    )
    (net (code "48") (name "Net-(U1-VDD)") (class "Default")
      (node (ref "C3") (pin "1") (pinfunction "1_1") (pintype "passive"))
      (node (ref "C4") (pin "1") (pinfunction "1_1") (pintype "passive"))
      (node (ref "R1") (pin "1") (pinfunction "1_1") (pintype "passive"))
      (node (ref "R4") (pin "2") (pinfunction "2_2") (pintype "passive"))
      (node (ref "R6") (pin "2") (pinfunction "2_2") (pintype "passive"))
      (node (ref "R7") (pin "2") (pinfunction "2_2") (pintype "passive"))
      (node (ref "U1") (pin "6") (pinfunction "VDD_6") (pintype "power_in"))
    )
    (net (code "49") (name "Net-(U2-PROG1)") (class "Default")
      (node (ref "R10") (pin "2") (pinfunction "2_2") (pintype "passive"))
      (node (ref "U2") (pin "13") (pinfunction "PROG1_13") (pintype "input"))
    )
    (net (code "50") (name "Net-(U2-PROG3)") (class "Default")
      (node (ref "R11") (pin "2") (pinfunction "2_2") (pintype "passive"))
      (node (ref "U2") (pin "12") (pinfunction "PROG3_12") (pintype "input"))
    )
    (net (code "51") (name "Net-(U2-THERM)") (class "Default")
      (node (ref "R15") (pin "2") (pinfunction "2_2") (pintype "passive"))
      (node (ref "U2") (pin "5") (pinfunction "THERM_5") (pintype "input"))
    )
    (net (code "52") (name "Net-(U2-VBAT1)") (class "Default")
      (node (ref "C8") (pin "1") (pinfunction "1_1") (pintype "passive"))
      (node (ref "F1") (pin "2") (pinfunction "2_2") (pintype "passive"))
      (node (ref "F2") (pin "2") (pinfunction "2_2") (pintype "passive"))
      (node (ref "R16") (pin "2") (pinfunction "2_2") (pintype "passive"))
      (node (ref "U2") (pin "14") (pinfunction "VBAT1_14") (pintype "output"))
      (node (ref "U2") (pin "15") (pinfunction "VBAT2_15") (pintype "output"))
      (node (ref "U2") (pin "16") (pinfunction "VBAT3_16") (pintype "output"))
    )
    (net (code "53") (name "Net-(U2-VPCC)") (class "Default")
      (node (ref "R8") (pin "1") (pinfunction "1_1") (pintype "passive"))
      (node (ref "R9") (pin "2") (pinfunction "2_2") (pintype "passive"))
      (node (ref "U2") (pin "2") (pinfunction "VPCC_2") (pintype "input"))
    )
    (net (code "54") (name "Net-(U2-{slash}TE)") (class "Default")
      (node (ref "R12") (pin "2") (pinfunction "2_2") (pintype "passive"))
      (node (ref "U2") (pin "9") (pinfunction "/TE_9") (pintype "input"))
    )
    (net (code "55") (name "Net-(U3-SS)") (class "Default")
      (node (ref "C12") (pin "1") (pinfunction "1_1") (pintype "passive"))
      (node (ref "U3") (pin "7") (pinfunction "SS_7") (pintype "passive"))
    )
    (net (code "56") (name "PG_N") (class "Default")
      (node (ref "R19") (pin "1") (pinfunction "1_1") (pintype "passive"))
      (node (ref "U2") (pin "6") (pinfunction "/PG_6") (pintype "output"))
    )
    (net (code "57") (name "PWR_EN") (class "Default")
      (node (ref "D4") (pin "C") (pinfunction "C_C") (pintype "passive"))
      (node (ref "D5") (pin "C") (pinfunction "C_C") (pintype "passive"))
      (node (ref "U3") (pin "11") (pinfunction "EN_11") (pintype "bidirectional"))
    )
    (net (code "58") (name "PWR_HOLD") (class "Default")
      (node (ref "A1") (pin "24") (pinfunction "IO2_24") (pintype "bidirectional"))
      (node (ref "D5") (pin "A") (pinfunction "A_A") (pintype "passive"))
    )
    (net (code "59") (name "RESET_N") (class "Default")
      (node (ref "A1") (pin "3") (pinfunction "EN_3") (pintype "input"))
      (node (ref "C16") (pin "1") (pinfunction "1_1") (pintype "passive"))
      (node (ref "J4") (pin "1") (pinfunction "1_1") (pintype "passive"))
      (node (ref "J6") (pin "1") (pinfunction "1_1") (pintype "passive"))
      (node (ref "Q5") (pin "C") (pinfunction "C_C") (pintype "passive"))
      (node (ref "R28") (pin "1") (pinfunction "1_1") (pintype "passive"))
    )
    (net (code "60") (name "RTS") (class "Default")
      (node (ref "Q2") (pin "3") (pinfunction "D_3") (pintype "passive"))
      (node (ref "Q6") (pin "1") (pinfunction "G_1") (pintype "passive"))
      (node (ref "R7") (pin "1") (pinfunction "1_1") (pintype "passive"))
    )
    (net (code "61") (name "RTS_N") (class "Default")
      (node (ref "Q5") (pin "E") (pinfunction "E_E") (pintype "passive"))
      (node (ref "Q6") (pin "3") (pinfunction "D_3") (pintype "passive"))
      (node (ref "R26") (pin "1") (pinfunction "1_1") (pintype "passive"))
      (node (ref "R27") (pin "2") (pinfunction "2_2") (pintype "passive"))
    )
    (net (code "62") (name "RXD") (class "Default")
      (node (ref "A1") (pin "35") (pinfunction "IO1/TXD0_35") (pintype "bidirectional"))
      (node (ref "D3") (pin "C") (pinfunction "C_C") (pintype "passive"))
    )
    (net (code "63") (name "SNS_BATT") (class "Default")
      (node (ref "A1") (pin "7") (pinfunction "IO35_7") (pintype "input"))
      (node (ref "C9") (pin "1") (pinfunction "1_1") (pintype "passive"))
      (node (ref "Q3") (pin "2") (pinfunction "S_2") (pintype "passive"))
      (node (ref "R17") (pin "2") (pinfunction "2_2") (pintype "passive"))
    )
    (net (code "64") (name "SNS_BTN") (class "Default")
      (node (ref "J3") (pin "1") (pinfunction "1_1") (pintype "passive"))
      (node (ref "R22") (pin "1") (pinfunction "1_1") (pintype "passive"))
      (node (ref "R23") (pin "2") (pinfunction "2_2") (pintype "passive"))
    )
    (net (code "65") (name "SNS_STAT") (class "Default")
      (node (ref "C10") (pin "1") (pinfunction "1_1") (pintype "passive"))
      (node (ref "J2") (pin "1") (pinfunction "1_1") (pintype "passive"))
      (node (ref "R18") (pin "1") (pinfunction "1_1") (pintype "passive"))
      (node (ref "R19") (pin "2") (pinfunction "2_2") (pintype "passive"))
      (node (ref "R20") (pin "2") (pinfunction "2_2") (pintype "passive"))
      (node (ref "R21") (pin "2") (pinfunction "2_2") (pintype "passive"))
    )
    (net (code "66") (name "STAT1") (class "Default")
      (node (ref "R21") (pin "1") (pinfunction "1_1") (pintype "passive"))
      (node (ref "U2") (pin "8") (pinfunction "STAT1/LBO_8") (pintype "output"))
    )
    (net (code "67") (name "STAT2") (class "Default")
      (node (ref "R20") (pin "1") (pinfunction "1_1") (pintype "passive"))
      (node (ref "U2") (pin "7") (pinfunction "STAT2_7") (pintype "output"))
    )
    (net (code "68") (name "TXD") (class "Default")
      (node (ref "A1") (pin "34") (pinfunction "IO3/RXD0_34") (pintype "bidirectional"))
      (node (ref "D2") (pin "A") (pinfunction "A_A") (pintype "passive"))
      (node (ref "R5") (pin "1") (pinfunction "1_1") (pintype "passive"))
    )
    (net (code "69") (name "V+") (class "Default")
      (node (ref "C11") (pin "1") (pinfunction "1_1") (pintype "passive"))
      (node (ref "C7") (pin "1") (pinfunction "1_1") (pintype "passive"))
      (node (ref "J5") (pin "12") (pinfunction "12_12") (pintype "passive"))
      (node (ref "J7") (pin "12") (pinfunction "12_12") (pintype "passive"))
      (node (ref "PB1") (pin "1") (pinfunction "1_1") (pintype "passive"))
      (node (ref "PB1") (pin "3") (pinfunction "2_3") (pintype "passive"))
      (node (ref "U2") (pin "1") (pinfunction "OUT1_1") (pintype "output"))
      (node (ref "U2") (pin "20") (pinfunction "OUT2_20") (pintype "output"))
      (node (ref "U3") (pin "12") (pinfunction "VIN_12") (pintype "power_in"))
      (node (ref "U3") (pin "6") (pinfunction "PFM/PWM_6") (pintype "bidirectional"))
    )
    (net (code "70") (name "unconnected-(A1-IO6{slash}SCK-Pad20)") (class "Default")
      (node (ref "A1") (pin "20") (pinfunction "IO6/SCK_20") (pintype "bidirectional"))
    )
    (net (code "71") (name "unconnected-(A1-IO7{slash}SDO-Pad21)") (class "Default")
      (node (ref "A1") (pin "21") (pinfunction "IO7/SDO_21") (pintype "bidirectional"))
    )
    (net (code "72") (name "unconnected-(A1-IO8{slash}SDI-Pad22)") (class "Default")
      (node (ref "A1") (pin "22") (pinfunction "IO8/SDI_22") (pintype "bidirectional"))
    )
    (net (code "73") (name "unconnected-(A1-IO9{slash}SHD-Pad17)") (class "Default")
      (node (ref "A1") (pin "17") (pinfunction "IO9/SHD_17") (pintype "bidirectional"))
    )
    (net (code "74") (name "unconnected-(A1-IO10{slash}SWP-Pad18)") (class "Default")
      (node (ref "A1") (pin "18") (pinfunction "IO10/SWP_18") (pintype "bidirectional"))
    )
    (net (code "75") (name "unconnected-(A1-IO11{slash}SCS-Pad19)") (class "Default")
      (node (ref "A1") (pin "19") (pinfunction "IO11/SCS_19") (pintype "bidirectional"))
    )
    (net (code "76") (name "unconnected-(U1-CHR1-Pad14)") (class "Default")
      (node (ref "U1") (pin "14") (pinfunction "CHR1_14") (pintype "output"))
    )
    (net (code "77") (name "unconnected-(U1-CTS-Pad23)") (class "Default")
      (node (ref "U1") (pin "23") (pinfunction "CTS_23") (pintype "input"))
    )
    (net (code "78") (name "unconnected-(U1-DCD-Pad1)") (class "Default")
      (node (ref "U1") (pin "1") (pinfunction "DCD_1") (pintype "input"))
    )
    (net (code "79") (name "unconnected-(U1-DSR-Pad27)") (class "Default")
      (node (ref "U1") (pin "27") (pinfunction "DSR_27") (pintype "input"))
    )
    (net (code "80") (name "unconnected-(U1-GPIO0-Pad19)") (class "Default")
      (node (ref "U1") (pin "19") (pinfunction "GPIO0_19") (pintype "bidirectional"))
    )
    (net (code "81") (name "unconnected-(U1-GPIO1-Pad18)") (class "Default")
      (node (ref "U1") (pin "18") (pinfunction "GPIO1_18") (pintype "bidirectional"))
    )
    (net (code "82") (name "unconnected-(U1-GPIO2-Pad17)") (class "Default")
      (node (ref "U1") (pin "17") (pinfunction "GPIO2_17") (pintype "bidirectional"))
    )
    (net (code "83") (name "unconnected-(U1-GPIO3-Pad16)") (class "Default")
      (node (ref "U1") (pin "16") (pinfunction "GPIO3_16") (pintype "bidirectional"))
    )
    (net (code "84") (name "unconnected-(U1-GPIO4-Pad22)") (class "Default")
      (node (ref "U1") (pin "22") (pinfunction "GPIO4_22") (pintype "bidirectional"))
    )
    (net (code "85") (name "unconnected-(U1-GPIO5-Pad21)") (class "Default")
      (node (ref "U1") (pin "21") (pinfunction "GPIO5_21") (pintype "bidirectional"))
    )
    (net (code "86") (name "unconnected-(U1-GPIO6-Pad20)") (class "Default")
      (node (ref "U1") (pin "20") (pinfunction "GPIO6_20") (pintype "bidirectional"))
    )
    (net (code "87") (name "unconnected-(U1-RI{slash}CLK-Pad2)") (class "Default")
      (node (ref "U1") (pin "2") (pinfunction "RI/CLK_2") (pintype "bidirectional"))
    )
    (net (code "88") (name "unconnected-(U1-SPD-Pad12)") (class "Default")
      (node (ref "U1") (pin "12") (pinfunction "SPD_12") (pintype "output"))
    )
    (net (code "89") (name "unconnected-(U1-SPDN-Pad11)") (class "Default")
      (node (ref "U1") (pin "11") (pinfunction "SPDN_11") (pintype "output"))
    )
    (net (code "90") (name "unconnected-(U3-PG-Pad8)") (class "Default")
      (node (ref "U3") (pin "8") (pinfunction "PG_8") (pintype "bidirectional"))
    )
  )
)
